# kelvin_1wire_A.net
KiCad netlist of a schematic drawn in EAGLE
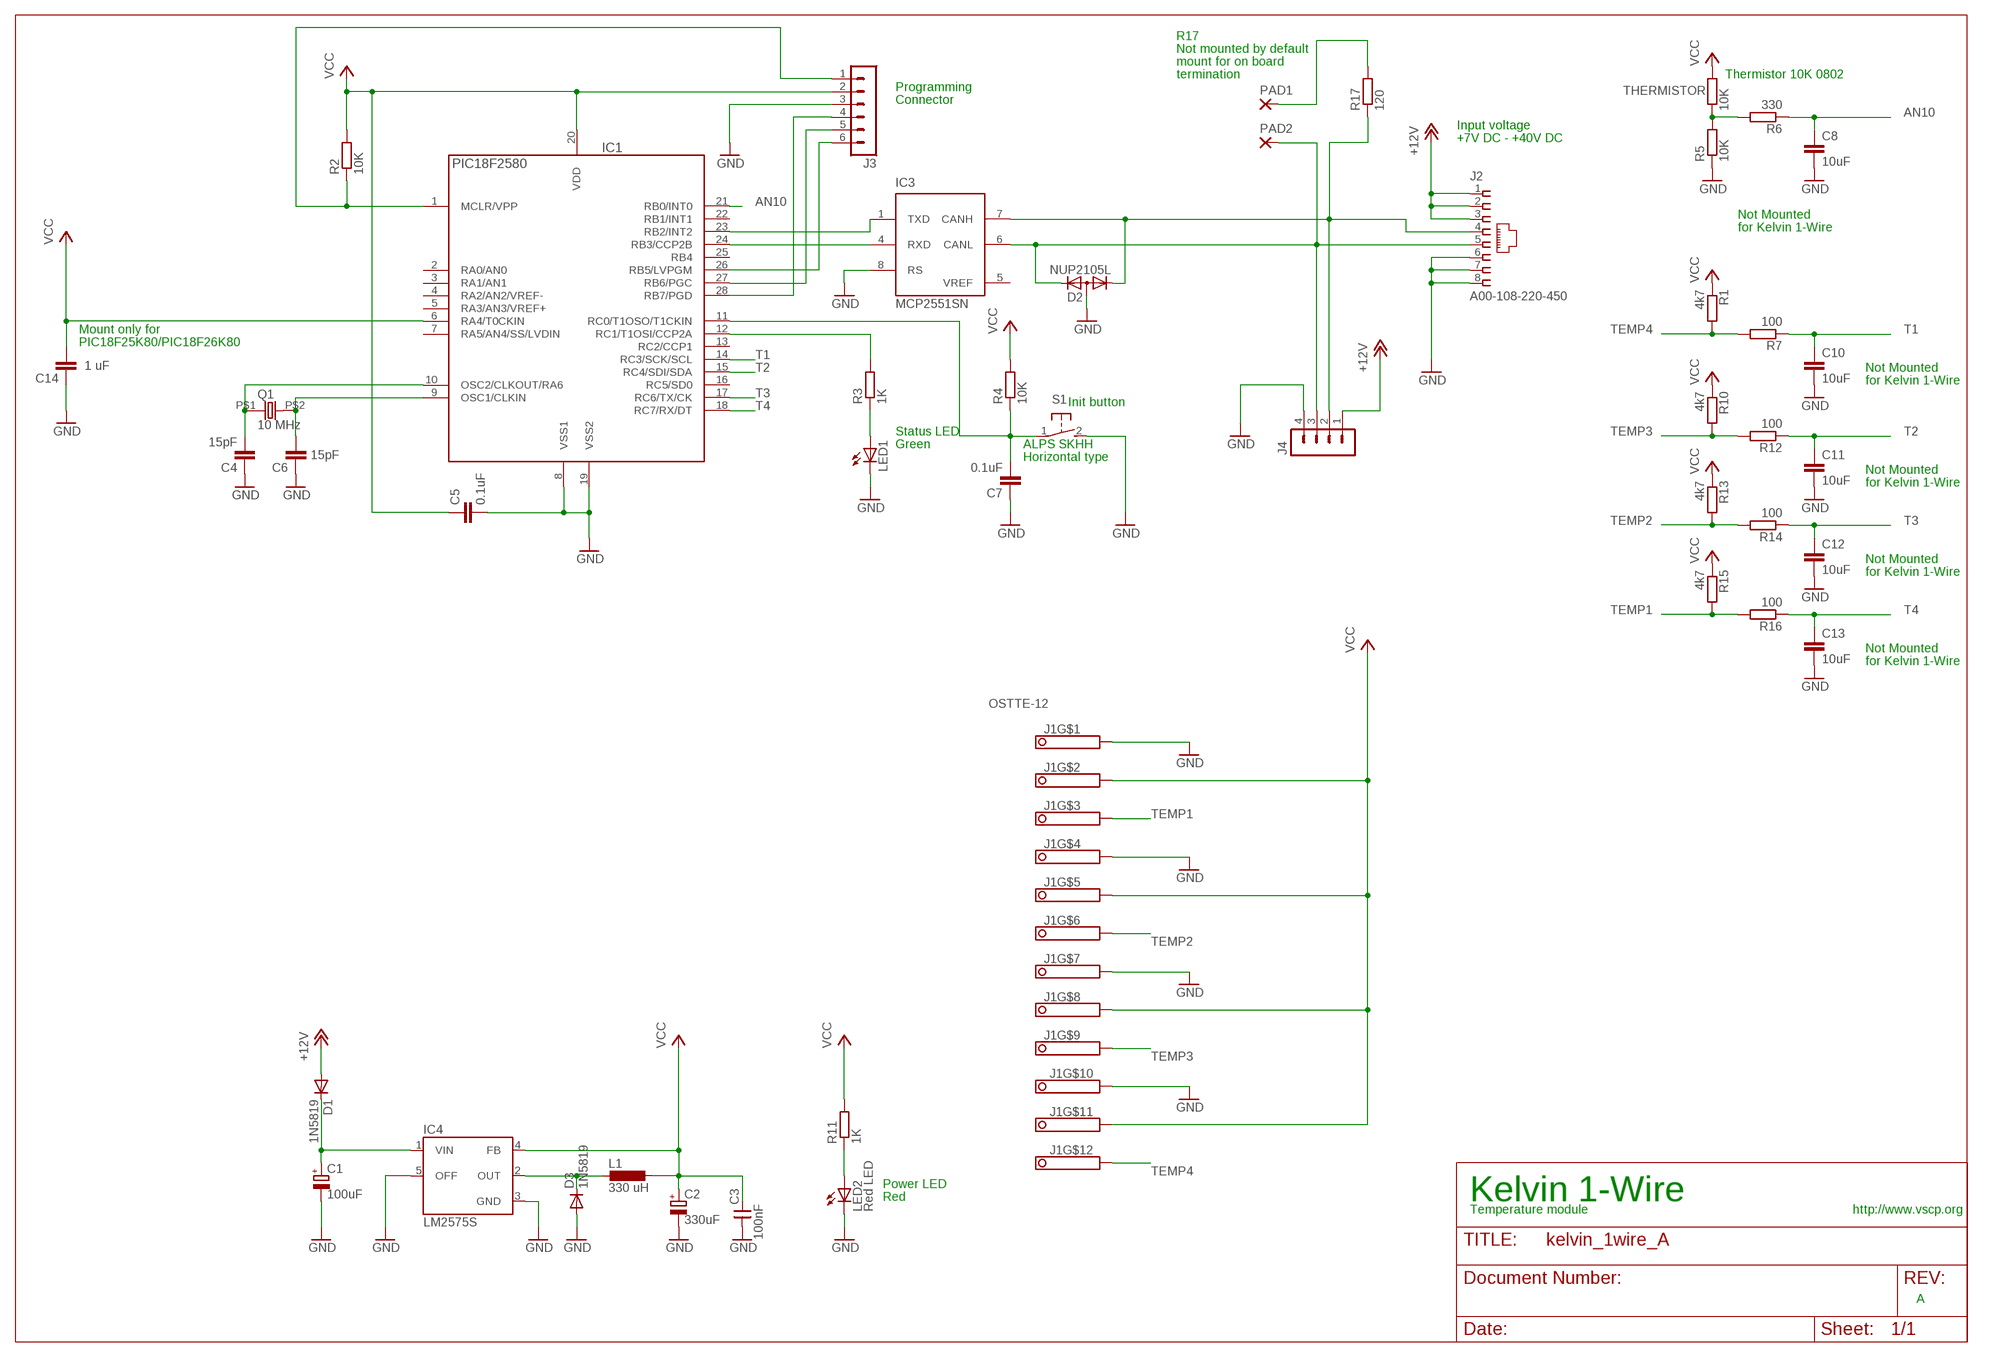
[diagram p0: schematic, sheet 1]

(export (version "E")
  (design (tool "Eeschema 10.0.6"))
  (components
    (comp (ref "C1")
      (value "100uF")
      (footprint "eagle-import:PANASONIC_D")
      (libsource (lib "eagle-import") (part "CPOL-EUD"))
    )
    (comp (ref "C2")
      (value "330uF")
      (footprint "eagle-import:PANASONIC_D")
      (libsource (lib "eagle-import") (part "CPOL-EUD"))
    )
    (comp (ref "C3")
      (value "100nF")
      (footprint "eagle-import:0805")
      (libsource (lib "eagle-import") (part "CNP-0805"))
    )
    (comp (ref "C4")
      (value "15pF")
      (footprint "eagle-import:C0805")
      (libsource (lib "eagle-import") (part "C-EUC0805"))
    )
    (comp (ref "C5")
      (value "0.1uF")
      (footprint "eagle-import:C0805")
      (libsource (lib "eagle-import") (part "C-EUC0805"))
    )
    (comp (ref "C6")
      (value "15pF")
      (footprint "eagle-import:C0805")
      (libsource (lib "eagle-import") (part "C-EUC0805"))
    )
    (comp (ref "C7")
      (value "0.1uF")
      (footprint "eagle-import:C0805")
      (libsource (lib "eagle-import") (part "C-EUC0805"))
    )
    (comp (ref "C8")
      (value "10uF")
      (footprint "eagle-import:C0805")
      (libsource (lib "eagle-import") (part "C-EUC0805"))
    )
    (comp (ref "C10")
      (value "10uF")
      (footprint "eagle-import:C0805")
      (libsource (lib "eagle-import") (part "C-EUC0805"))
    )
    (comp (ref "C11")
      (value "10uF")
      (footprint "eagle-import:C0805")
      (libsource (lib "eagle-import") (part "C-EUC0805"))
    )
    (comp (ref "C12")
      (value "10uF")
      (footprint "eagle-import:C0805")
      (libsource (lib "eagle-import") (part "C-EUC0805"))
    )
    (comp (ref "C13")
      (value "10uF")
      (footprint "eagle-import:C0805")
      (libsource (lib "eagle-import") (part "C-EUC0805"))
    )
    (comp (ref "C14")
      (value "1 uF")
      (footprint "eagle-import:C0805")
      (libsource (lib "eagle-import") (part "C-EUC0805"))
    )
    (comp (ref "D1")
      (value "1N5819")
      (footprint "eagle-import:SOD123")
      (libsource (lib "eagle-import") (part "DIODE-SOD123"))
    )
    (comp (ref "D2")
      (value "NUP2105L")
      (footprint "eagle-import:SOT23")
      (libsource (lib "eagle-import") (part "DIODE-2CA|ACSOT23"))
    )
    (comp (ref "D3")
      (value "1N5819")
      (footprint "eagle-import:SOD123")
      (libsource (lib "eagle-import") (part "DIODE-SOD123"))
    )
    (comp (ref "IC1")
      (value "PIC18F2580")
      (footprint "eagle-import:SO28")
      (libsource (lib "eagle-import") (part "PIC18F252-?I/SOL"))
    )
    (comp (ref "IC3")
      (value "MCP2551SN")
      (footprint "eagle-import:SO-08")
      (libsource (lib "eagle-import") (part "MCP2551SN"))
    )
    (comp (ref "IC4")
      (value "LM2575S")
      (footprint "eagle-import:TO263-5")
      (libsource (lib "eagle-import") (part "LM2575S"))
    )
    (comp (ref "J1")
      (value "OSTTE-12")
      (footprint "eagle-import:PINHEAD-12")
      (libsource (lib "eagle-import") (part "OSTTE-12"))
    )
    (comp (ref "J2")
      (value "A00-108-220-450")
      (footprint "eagle-import:RJ-45")
      (libsource (lib "eagle-import") (part "A00-108-220-450"))
    )
    (comp (ref "J3")
      (value "MA06-1")
      (footprint "eagle-import:MA06-1")
      (libsource (lib "eagle-import") (part "MA06-1"))
    )
    (comp (ref "J4")
      (value "MA04-1")
      (footprint "eagle-import:MA04-1")
      (libsource (lib "eagle-import") (part "MA04-1"))
    )
    (comp (ref "L1")
      (value "330 uH")
      (footprint "eagle-import:DO3316P")
      (libsource (lib "eagle-import") (part "DO3316P"))
    )
    (comp (ref "LED1")
      (value "LEDCHIP-LED0805")
      (footprint "eagle-import:CHIP-LED0805")
      (libsource (lib "eagle-import") (part "LEDCHIP-LED0805"))
    )
    (comp (ref "LED2")
      (value "Red LED")
      (footprint "eagle-import:CHIP-LED0805")
      (libsource (lib "eagle-import") (part "LEDCHIP-LED0805"))
    )
    (comp (ref "PAD1")
      (value "1,6/0,8")
      (footprint "eagle-import:1,6_0,8")
      (libsource (lib "eagle-import") (part "1,6/0,8"))
    )
    (comp (ref "PAD2")
      (value "1,6/0,8")
      (footprint "eagle-import:1,6_0,8")
      (libsource (lib "eagle-import") (part "1,6/0,8"))
    )
    (comp (ref "Q1")
      (value "10 MHz")
      (footprint "eagle-import:9C")
      (libsource (lib "eagle-import") (part "HC-49S"))
    )
    (comp (ref "R1")
      (value "4k7")
      (footprint "eagle-import:R0805")
      (libsource (lib "eagle-import") (part "R-EU_R0805"))
    )
    (comp (ref "R2")
      (value "10K")
      (footprint "eagle-import:R0805")
      (libsource (lib "eagle-import") (part "R-EU_R0805"))
    )
    (comp (ref "R3")
      (value "1K")
      (footprint "eagle-import:R0805")
      (libsource (lib "eagle-import") (part "R-EU_R0805"))
    )
    (comp (ref "R4")
      (value "10K")
      (footprint "eagle-import:R0805")
      (libsource (lib "eagle-import") (part "R-EU_R0805"))
    )
    (comp (ref "R5")
      (value "10K")
      (footprint "eagle-import:R0805")
      (libsource (lib "eagle-import") (part "R-EU_R0805"))
    )
    (comp (ref "R6")
      (value "330")
      (footprint "eagle-import:R0805")
      (libsource (lib "eagle-import") (part "R-EU_R0805"))
    )
    (comp (ref "R7")
      (value "100")
      (footprint "eagle-import:R0805")
      (libsource (lib "eagle-import") (part "R-EU_R0805"))
    )
    (comp (ref "R10")
      (value "4k7")
      (footprint "eagle-import:R0805")
      (libsource (lib "eagle-import") (part "R-EU_R0805"))
    )
    (comp (ref "R11")
      (value "1K")
      (footprint "eagle-import:R0805")
      (libsource (lib "eagle-import") (part "R-EU_R0805"))
    )
    (comp (ref "R12")
      (value "100")
      (footprint "eagle-import:R0805")
      (libsource (lib "eagle-import") (part "R-EU_R0805"))
    )
    (comp (ref "R13")
      (value "4k7")
      (footprint "eagle-import:R0805")
      (libsource (lib "eagle-import") (part "R-EU_R0805"))
    )
    (comp (ref "R14")
      (value "100")
      (footprint "eagle-import:R0805")
      (libsource (lib "eagle-import") (part "R-EU_R0805"))
    )
    (comp (ref "R15")
      (value "4k7")
      (footprint "eagle-import:R0805")
      (libsource (lib "eagle-import") (part "R-EU_R0805"))
    )
    (comp (ref "R16")
      (value "100")
      (footprint "eagle-import:R0805")
      (libsource (lib "eagle-import") (part "R-EU_R0805"))
    )
    (comp (ref "R17")
      (value "120")
      (footprint "eagle-import:R0805")
      (libsource (lib "eagle-import") (part "R-EU_R0805"))
    )
    (comp (ref "S1")
      (value "31-XX")
      (footprint "eagle-import:B3F-31XX")
      (fields (field (name "MPN") "B3F-3100"))
      (libsource (lib "eagle-import") (part "31-XX"))
    )
    (comp (ref "THERMISTOR")
      (value "10K")
      (footprint "eagle-import:R0805")
      (libsource (lib "eagle-import") (part "R-EU_R0805"))
    )
  )
  (nets
    (net (code "1") (name "+12V") (class "Default")
      (node (ref "D1") (pin "A") (pinfunction "A_A") (pintype "passive"))
      (node (ref "J2") (pin "1") (pinfunction "1_1") (pintype "passive"))
      (node (ref "J2") (pin "2") (pinfunction "2_2") (pintype "passive"))
      (node (ref "J2") (pin "3") (pinfunction "3_3") (pintype "passive"))
      (node (ref "J4") (pin "1") (pinfunction "1_1") (pintype "passive"))
    )
    (net (code "2") (name "/AN10") (class "Default")
      (node (ref "C8") (pin "1") (pinfunction "1_1") (pintype "passive"))
      (node (ref "IC1") (pin "21") (pinfunction "RB0/INT0_21") (pintype "bidirectional"))
      (node (ref "R6") (pin "1") (pinfunction "1_1") (pintype "passive"))
    )
    (net (code "3") (name "/T1") (class "Default")
      (node (ref "C10") (pin "1") (pinfunction "1_1") (pintype "passive"))
      (node (ref "IC1") (pin "14") (pinfunction "RC3/SCK/SCL_14") (pintype "bidirectional"))
      (node (ref "R7") (pin "1") (pinfunction "1_1") (pintype "passive"))
    )
    (net (code "4") (name "/T2") (class "Default")
      (node (ref "C11") (pin "1") (pinfunction "1_1") (pintype "passive"))
      (node (ref "IC1") (pin "15") (pinfunction "RC4/SDI/SDA_15") (pintype "bidirectional"))
      (node (ref "R12") (pin "1") (pinfunction "1_1") (pintype "passive"))
    )
    (net (code "5") (name "/T3") (class "Default")
      (node (ref "C12") (pin "1") (pinfunction "1_1") (pintype "passive"))
      (node (ref "IC1") (pin "17") (pinfunction "RC6/TX/CK_17") (pintype "bidirectional"))
      (node (ref "R14") (pin "1") (pinfunction "1_1") (pintype "passive"))
    )
    (net (code "6") (name "/T4") (class "Default")
      (node (ref "C13") (pin "1") (pinfunction "1_1") (pintype "passive"))
      (node (ref "IC1") (pin "18") (pinfunction "RC7/RX/DT_18") (pintype "bidirectional"))
      (node (ref "R16") (pin "1") (pinfunction "1_1") (pintype "passive"))
    )
    (net (code "7") (name "/TEMP1") (class "Default")
      (node (ref "J1") (pin "3") (pinfunction "K_3") (pintype "passive"))
      (node (ref "R15") (pin "2") (pinfunction "2_2") (pintype "passive"))
      (node (ref "R16") (pin "2") (pinfunction "2_2") (pintype "passive"))
    )
    (net (code "8") (name "/TEMP2") (class "Default")
      (node (ref "J1") (pin "6") (pinfunction "K_6") (pintype "passive"))
      (node (ref "R13") (pin "2") (pinfunction "2_2") (pintype "passive"))
      (node (ref "R14") (pin "2") (pinfunction "2_2") (pintype "passive"))
    )
    (net (code "9") (name "/TEMP3") (class "Default")
      (node (ref "J1") (pin "9") (pinfunction "K_9") (pintype "passive"))
      (node (ref "R10") (pin "2") (pinfunction "2_2") (pintype "passive"))
      (node (ref "R12") (pin "2") (pinfunction "2_2") (pintype "passive"))
    )
    (net (code "10") (name "/TEMP4") (class "Default")
      (node (ref "J1") (pin "12") (pinfunction "K_12") (pintype "passive"))
      (node (ref "R1") (pin "2") (pinfunction "2_2") (pintype "passive"))
      (node (ref "R7") (pin "2") (pinfunction "2_2") (pintype "passive"))
    )
    (net (code "11") (name "/VREF") (class "Default")
      (node (ref "IC3") (pin "5") (pinfunction "VREF_5") (pintype "power_in"))
    )
    (net (code "12") (name "GND") (class "Default")
      (node (ref "C1") (pin "-") (pinfunction "-_-") (pintype "passive"))
      (node (ref "C10") (pin "2") (pinfunction "2_2") (pintype "passive"))
      (node (ref "C11") (pin "2") (pinfunction "2_2") (pintype "passive"))
      (node (ref "C12") (pin "2") (pinfunction "2_2") (pintype "passive"))
      (node (ref "C13") (pin "2") (pinfunction "2_2") (pintype "passive"))
      (node (ref "C14") (pin "1") (pinfunction "1_1") (pintype "passive"))
      (node (ref "C2") (pin "-") (pinfunction "-_-") (pintype "passive"))
      (node (ref "C3") (pin "1") (pinfunction "1_1") (pintype "passive"))
      (node (ref "C4") (pin "1") (pinfunction "1_1") (pintype "passive"))
      (node (ref "C5") (pin "2") (pinfunction "2_2") (pintype "passive"))
      (node (ref "C6") (pin "1") (pinfunction "1_1") (pintype "passive"))
      (node (ref "C7") (pin "1") (pinfunction "1_1") (pintype "passive"))
      (node (ref "C8") (pin "2") (pinfunction "2_2") (pintype "passive"))
      (node (ref "D2") (pin "3") (pinfunction "A_3") (pintype "passive"))
      (node (ref "D3") (pin "A") (pinfunction "A_A") (pintype "passive"))
      (node (ref "IC1") (pin "19") (pinfunction "VSS2_19") (pintype "power_in"))
      (node (ref "IC1") (pin "8") (pinfunction "VSS1_8") (pintype "power_in"))
      (node (ref "IC3") (pin "8") (pinfunction "RS_8") (pintype "input"))
      (node (ref "IC4") (pin "3") (pinfunction "GND_3") (pintype "power_in"))
      (node (ref "IC4") (pin "5") (pinfunction "OFF_5") (pintype "input"))
      (node (ref "J1") (pin "1") (pinfunction "K_1") (pintype "passive"))
      (node (ref "J1") (pin "10") (pinfunction "K_10") (pintype "passive"))
      (node (ref "J1") (pin "4") (pinfunction "K_4") (pintype "passive"))
      (node (ref "J1") (pin "7") (pinfunction "K_7") (pintype "passive"))
      (node (ref "J2") (pin "6") (pinfunction "6_6") (pintype "passive"))
      (node (ref "J2") (pin "7") (pinfunction "7_7") (pintype "passive"))
      (node (ref "J2") (pin "8") (pinfunction "8_8") (pintype "passive"))
      (node (ref "J3") (pin "3") (pinfunction "3_3") (pintype "passive"))
      (node (ref "J4") (pin "4") (pinfunction "4_4") (pintype "passive"))
      (node (ref "LED1") (pin "C") (pinfunction "C_C") (pintype "passive"))
      (node (ref "LED2") (pin "C") (pinfunction "C_C") (pintype "passive"))
      (node (ref "R5") (pin "1") (pinfunction "1_1") (pintype "passive"))
      (node (ref "S1") (pin "2") (pinfunction "S_2") (pintype "passive"))
    )
    (net (code "13") (name "Net-(D2-K1)") (class "Default")
      (node (ref "D2") (pin "1") (pinfunction "K1_1") (pintype "passive"))
      (node (ref "IC3") (pin "7") (pinfunction "CANH_7") (pintype "bidirectional"))
      (node (ref "J2") (pin "4") (pinfunction "4_4") (pintype "passive"))
      (node (ref "J4") (pin "2") (pinfunction "2_2") (pintype "passive"))
      (node (ref "R17") (pin "1") (pinfunction "1_1") (pintype "passive"))
    )
    (net (code "14") (name "Net-(D2-K2)") (class "Default")
      (node (ref "D2") (pin "2") (pinfunction "K2_2") (pintype "passive"))
      (node (ref "IC3") (pin "6") (pinfunction "CANL_6") (pintype "bidirectional"))
      (node (ref "J2") (pin "5") (pinfunction "5_5") (pintype "passive"))
      (node (ref "J4") (pin "3") (pinfunction "3_3") (pintype "passive"))
      (node (ref "PAD2") (pin "1") (pinfunction "P_1") (pintype "passive"))
    )
    (net (code "15") (name "Net-(IC1-MCLR{slash}VPP)") (class "Default")
      (node (ref "IC1") (pin "1") (pinfunction "MCLR/VPP_1") (pintype "input"))
      (node (ref "J3") (pin "1") (pinfunction "1_1") (pintype "passive"))
      (node (ref "R2") (pin "1") (pinfunction "1_1") (pintype "passive"))
    )
    (net (code "16") (name "Net-(IC1-OSC1{slash}CLKIN)") (class "Default")
      (node (ref "C6") (pin "2") (pinfunction "2_2") (pintype "passive"))
      (node (ref "IC1") (pin "9") (pinfunction "OSC1/CLKIN_9") (pintype "input"))
      (node (ref "Q1") (pin "P$2") (pinfunction "2_P$2") (pintype "passive"))
    )
    (net (code "17") (name "Net-(IC1-OSC2{slash}CLKOUT{slash}RA6)") (class "Default")
      (node (ref "C4") (pin "2") (pinfunction "2_2") (pintype "passive"))
      (node (ref "IC1") (pin "10") (pinfunction "OSC2/CLKOUT/RA6_10") (pintype "output"))
      (node (ref "Q1") (pin "P$1") (pinfunction "1_P$1") (pintype "passive"))
    )
    (net (code "18") (name "Net-(IC1-RB2{slash}INT2)") (class "Default")
      (node (ref "IC1") (pin "23") (pinfunction "RB2/INT2_23") (pintype "bidirectional"))
      (node (ref "IC3") (pin "1") (pinfunction "TXD_1") (pintype "input"))
    )
    (net (code "19") (name "Net-(IC1-RB3{slash}CCP2B)") (class "Default")
      (node (ref "IC1") (pin "24") (pinfunction "RB3/CCP2B_24") (pintype "bidirectional"))
      (node (ref "IC3") (pin "4") (pinfunction "RXD_4") (pintype "output"))
    )
    (net (code "20") (name "Net-(IC1-RB5{slash}LVPGM)") (class "Default")
      (node (ref "IC1") (pin "26") (pinfunction "RB5/LVPGM_26") (pintype "bidirectional"))
      (node (ref "J3") (pin "6") (pinfunction "6_6") (pintype "passive"))
    )
    (net (code "21") (name "Net-(IC1-RB6{slash}PGC)") (class "Default")
      (node (ref "IC1") (pin "27") (pinfunction "RB6/PGC_27") (pintype "bidirectional"))
      (node (ref "J3") (pin "5") (pinfunction "5_5") (pintype "passive"))
    )
    (net (code "22") (name "Net-(IC1-RB7{slash}PGD)") (class "Default")
      (node (ref "IC1") (pin "28") (pinfunction "RB7/PGD_28") (pintype "bidirectional"))
      (node (ref "J3") (pin "4") (pinfunction "4_4") (pintype "passive"))
    )
    (net (code "23") (name "Net-(IC1-RC0{slash}T1OSO{slash}T1CKIN)") (class "Default")
      (node (ref "C7") (pin "2") (pinfunction "2_2") (pintype "passive"))
      (node (ref "IC1") (pin "11") (pinfunction "RC0/T1OSO/T1CKIN_11") (pintype "bidirectional"))
      (node (ref "R4") (pin "1") (pinfunction "1_1") (pintype "passive"))
      (node (ref "S1") (pin "1") (pinfunction "P_1") (pintype "passive"))
    )
    (net (code "24") (name "Net-(IC1-RC1{slash}T1OSI{slash}CCP2A)") (class "Default")
      (node (ref "IC1") (pin "12") (pinfunction "RC1/T1OSI/CCP2A_12") (pintype "bidirectional"))
      (node (ref "R3") (pin "2") (pinfunction "2_2") (pintype "passive"))
    )
    (net (code "25") (name "Net-(IC4-OUT)") (class "Default")
      (node (ref "D3") (pin "C") (pinfunction "C_C") (pintype "passive"))
      (node (ref "IC4") (pin "2") (pinfunction "OUT_2") (pintype "output"))
      (node (ref "L1") (pin "1") (pinfunction "1_1") (pintype "passive"))
    )
    (net (code "26") (name "Net-(IC4-VIN)") (class "Default")
      (node (ref "C1") (pin "+") (pinfunction "+_+") (pintype "passive"))
      (node (ref "D1") (pin "C") (pinfunction "C_C") (pintype "passive"))
      (node (ref "IC4") (pin "1") (pinfunction "VIN_1") (pintype "power_in"))
    )
    (net (code "27") (name "Net-(LED1-PadA)") (class "Default")
      (node (ref "LED1") (pin "A") (pinfunction "A_A") (pintype "passive"))
      (node (ref "R3") (pin "1") (pinfunction "1_1") (pintype "passive"))
    )
    (net (code "28") (name "Net-(LED2-PadA)") (class "Default")
      (node (ref "LED2") (pin "A") (pinfunction "A_A") (pintype "passive"))
      (node (ref "R11") (pin "1") (pinfunction "1_1") (pintype "passive"))
    )
    (net (code "29") (name "Net-(PAD1-P)") (class "Default")
      (node (ref "PAD1") (pin "1") (pinfunction "P_1") (pintype "passive"))
      (node (ref "R17") (pin "2") (pinfunction "2_2") (pintype "passive"))
    )
    (net (code "30") (name "Net-(R5-Pad2)") (class "Default")
      (node (ref "R5") (pin "2") (pinfunction "2_2") (pintype "passive"))
      (node (ref "R6") (pin "2") (pinfunction "2_2") (pintype "passive"))
      (node (ref "THERMISTOR") (pin "1") (pinfunction "1_1") (pintype "passive"))
    )
    (net (code "31") (name "VCC") (class "Default")
      (node (ref "C14") (pin "2") (pinfunction "2_2") (pintype "passive"))
      (node (ref "C2") (pin "+") (pinfunction "+_+") (pintype "passive"))
      (node (ref "C3") (pin "2") (pinfunction "2_2") (pintype "passive"))
      (node (ref "C5") (pin "1") (pinfunction "1_1") (pintype "passive"))
      (node (ref "IC1") (pin "20") (pinfunction "VDD_20") (pintype "power_in"))
      (node (ref "IC1") (pin "6") (pinfunction "RA4/T0CKIN_6") (pintype "open_collector"))
      (node (ref "IC4") (pin "4") (pinfunction "FB_4") (pintype "input"))
      (node (ref "J1") (pin "11") (pinfunction "K_11") (pintype "passive"))
      (node (ref "J1") (pin "2") (pinfunction "K_2") (pintype "passive"))
      (node (ref "J1") (pin "5") (pinfunction "K_5") (pintype "passive"))
      (node (ref "J1") (pin "8") (pinfunction "K_8") (pintype "passive"))
      (node (ref "J3") (pin "2") (pinfunction "2_2") (pintype "passive"))
      (node (ref "L1") (pin "2") (pinfunction "2_2") (pintype "passive"))
      (node (ref "R1") (pin "1") (pinfunction "1_1") (pintype "passive"))
      (node (ref "R10") (pin "1") (pinfunction "1_1") (pintype "passive"))
      (node (ref "R11") (pin "2") (pinfunction "2_2") (pintype "passive"))
      (node (ref "R13") (pin "1") (pinfunction "1_1") (pintype "passive"))
      (node (ref "R15") (pin "1") (pinfunction "1_1") (pintype "passive"))
      (node (ref "R2") (pin "2") (pinfunction "2_2") (pintype "passive"))
      (node (ref "R4") (pin "2") (pinfunction "2_2") (pintype "passive"))
      (node (ref "THERMISTOR") (pin "2") (pinfunction "2_2") (pintype "passive"))
    )
    (net (code "32") (name "unconnected-(IC1-RA0{slash}AN0-Pad2)") (class "Default")
      (node (ref "IC1") (pin "2") (pinfunction "RA0/AN0_2") (pintype "bidirectional"))
    )
    (net (code "33") (name "unconnected-(IC1-RA1{slash}AN1-Pad3)") (class "Default")
      (node (ref "IC1") (pin "3") (pinfunction "RA1/AN1_3") (pintype "bidirectional"))
    )
    (net (code "34") (name "unconnected-(IC1-RA2{slash}AN2{slash}VREF--Pad4)") (class "Default")
      (node (ref "IC1") (pin "4") (pinfunction "RA2/AN2/VREF-_4") (pintype "bidirectional"))
    )
    (net (code "35") (name "unconnected-(IC1-RA3{slash}AN3{slash}VREF+-Pad5)") (class "Default")
      (node (ref "IC1") (pin "5") (pinfunction "RA3/AN3/VREF+_5") (pintype "bidirectional"))
    )
    (net (code "36") (name "unconnected-(IC1-RA5{slash}AN4{slash}SS{slash}LVDIN-Pad7)") (class "Default")
      (node (ref "IC1") (pin "7") (pinfunction "RA5/AN4/SS/LVDIN_7") (pintype "bidirectional"))
    )
    (net (code "37") (name "unconnected-(IC1-RB1{slash}INT1-Pad22)") (class "Default")
      (node (ref "IC1") (pin "22") (pinfunction "RB1/INT1_22") (pintype "bidirectional"))
    )
    (net (code "38") (name "unconnected-(IC1-RB4-Pad25)") (class "Default")
      (node (ref "IC1") (pin "25") (pinfunction "RB4_25") (pintype "bidirectional"))
    )
    (net (code "39") (name "unconnected-(IC1-RC2{slash}CCP1-Pad13)") (class "Default")
      (node (ref "IC1") (pin "13") (pinfunction "RC2/CCP1_13") (pintype "bidirectional"))
    )
    (net (code "40") (name "unconnected-(IC1-RC5{slash}SD0-Pad16)") (class "Default")
      (node (ref "IC1") (pin "16") (pinfunction "RC5/SD0_16") (pintype "bidirectional"))
    )
  )
)
